# Shift_register_schematic.net
KiCad netlist of a schematic drawn in Altium Designer
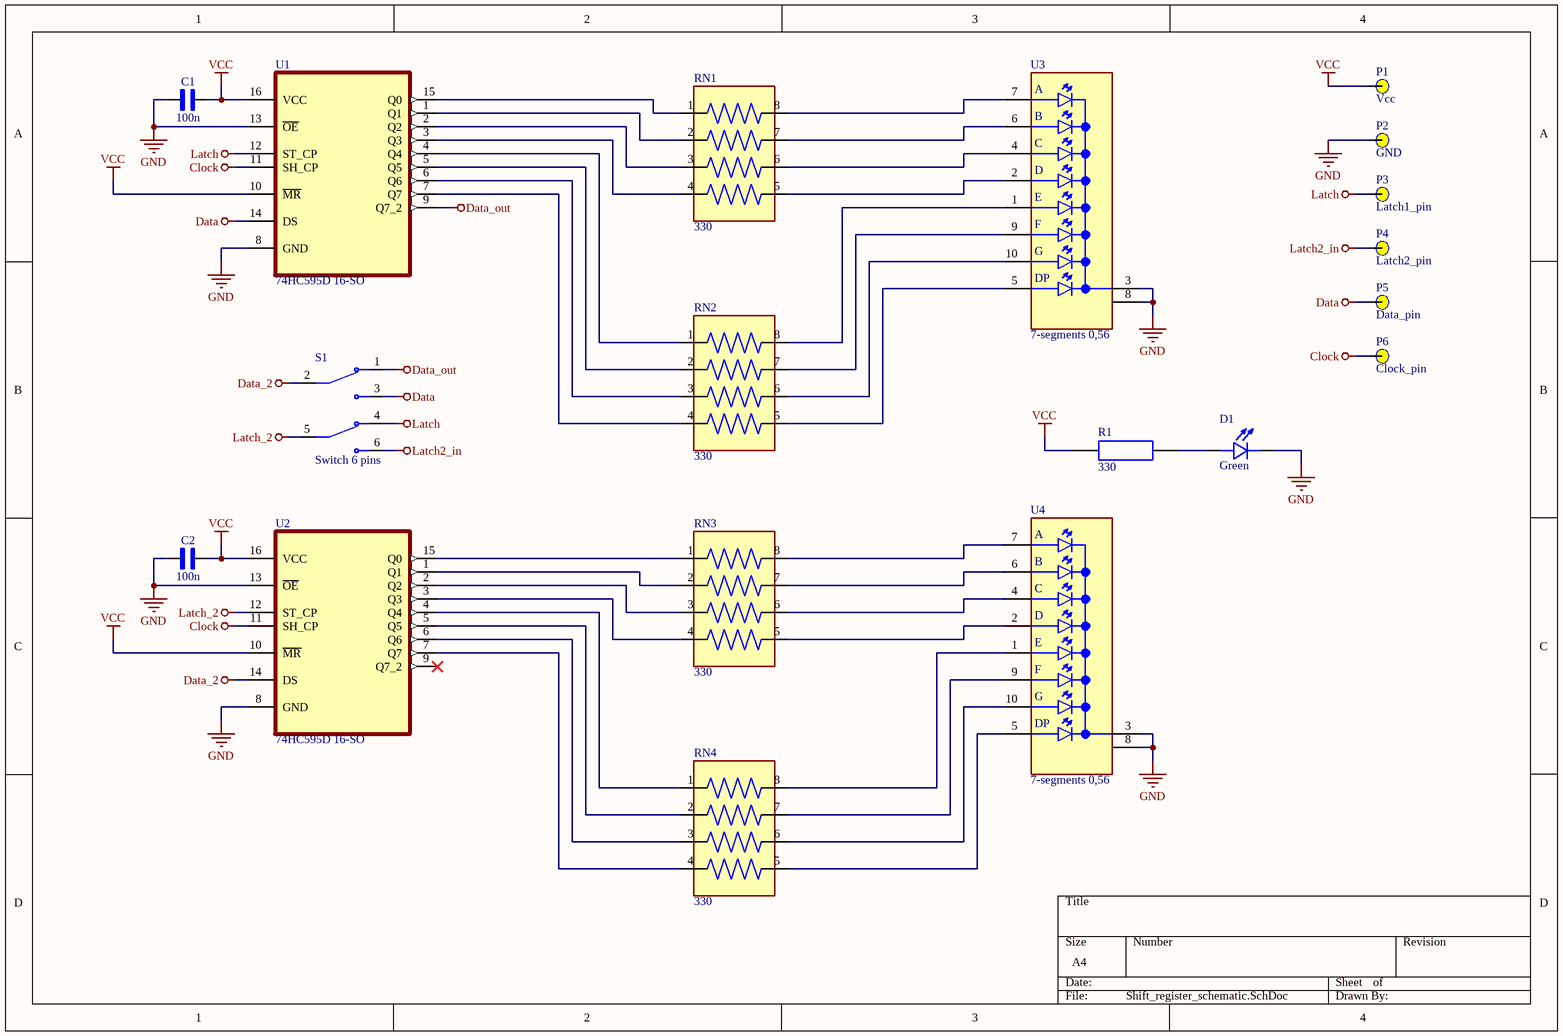
[diagram p0: Shift_register_schematic.SchDoc]

(export (version "E")
  (design (tool "Eeschema 10.0.6"))
  (components
    (comp (ref "C1")
      (value "100n")
      (footprint "Capacitor 1206")
      (fields (field (name "MF") "AVX") (field (name "MP") "12061C225K4T2A"))
      (libsource (lib "Schlib") (part "Capacitor 1206"))
    )
    (comp (ref "C2")
      (value "100n")
      (footprint "Capacitor 1206")
      (fields (field (name "MF") "AVX") (field (name "MP") "12061C225K4T2A"))
      (libsource (lib "Schlib") (part "Capacitor 1206"))
    )
    (comp (ref "D1")
      (value "Green")
      (footprint "LED 1206")
      (fields (field (name "MF") "Lite-On Inc.") (field (name "MP") "LTST-C230KGKT"))
      (libsource (lib "Schlib") (part "LED 1206"))
    )
    (comp (ref "P1") (value "Vcc") (footprint "PCB_Pin_1") (libsource (lib "Schlib") (part "PIN_1")))
    (comp (ref "P2") (value "GND") (footprint "PCB_Pin_1") (libsource (lib "Schlib") (part "PIN_1")))
    (comp (ref "P3") (value "Latch1_pin") (footprint "PCB_Pin_1") (libsource (lib "Schlib") (part "PIN_1")))
    (comp (ref "P4") (value "Latch2_pin") (footprint "PCB_Pin_1") (libsource (lib "Schlib") (part "PIN_1")))
    (comp (ref "P5") (value "Data_pin") (footprint "PCB_Pin_1") (libsource (lib "Schlib") (part "PIN_1")))
    (comp (ref "P6") (value "Clock_pin") (footprint "PCB_Pin_1") (libsource (lib "Schlib") (part "PIN_1")))
    (comp (ref "R1")
      (value "330")
      (footprint "Resistor 1206")
      (fields (field (name "MP") "ERJU08F4703V"))
      (libsource (lib "Schlib") (part "Resistor 1206"))
    )
    (comp (ref "RN1")
      (value "330")
      (footprint "Resistor array 1206")
      (description "Resistor,Thick Film,Networks & Arrays,330 Ohm,5%,8 Pin ¦ Bourns CAY16-331J4LF")
      (fields (field (name "MF") "Bourns") (field (name "MP") "CAY16-331J4LF"))
      (libsource (lib "Schlib") (part "Resistor array 1206"))
    )
    (comp (ref "RN2")
      (value "330")
      (footprint "Resistor array 1206")
      (description "Resistor,Thick Film,Networks & Arrays,330 Ohm,5%,8 Pin ¦ Bourns CAY16-331J4LF")
      (fields (field (name "MF") "Bourns") (field (name "MP") "CAY16-331J4LF"))
      (libsource (lib "Schlib") (part "Resistor array 1206"))
    )
    (comp (ref "RN3")
      (value "330")
      (footprint "Resistor array 1206")
      (description "Resistor,Thick Film,Networks & Arrays,330 Ohm,5%,8 Pin ¦ Bourns CAY16-331J4LF")
      (fields (field (name "MF") "Bourns") (field (name "MP") "CAY16-331J4LF"))
      (libsource (lib "Schlib") (part "Resistor array 1206"))
    )
    (comp (ref "RN4")
      (value "330")
      (footprint "Resistor array 1206")
      (description "Resistor,Thick Film,Networks & Arrays,330 Ohm,5%,8 Pin ¦ Bourns CAY16-331J4LF")
      (fields (field (name "MF") "Bourns") (field (name "MP") "CAY16-331J4LF"))
      (libsource (lib "Schlib") (part "Resistor array 1206"))
    )
    (comp (ref "S1")
      (value "Switch 6 pins")
      (footprint "Switch 6 pins")
      (description "Switch MSK-22D18G2")
      (fields (field (name "MF") "E-Switch") (field (name "MP") "TL2201EEZA"))
      (libsource (lib "Schlib") (part "Switch 6 pins"))
    )
    (comp (ref "U1")
      (value "74HC595D 16-SO")
      (footprint "74HC595 SO-16")
      (description "Shift Shift Register 1 Element 8 Bit 16-SO")
      (fields (field (name "MF") "NXP USA") (field (name "MP") "74HC595D/AUJ"))
      (libsource (lib "Schlib") (part "74HC595D 16-SO"))
    )
    (comp (ref "U2")
      (value "74HC595D 16-SO")
      (footprint "74HC595 SO-16")
      (description "Shift Shift Register 1 Element 8 Bit 16-SO")
      (fields (field (name "MF") "NXP USA") (field (name "MP") "74HC595D/AUJ"))
      (libsource (lib "Schlib") (part "74HC595D 16-SO"))
    )
    (comp (ref "U3")
      (value "7-segments 0,56")
      (footprint "7-segments 0,56")
      (description ".56IN. 7 SEGMENT SINGLE DISPLAY, 565NM GREEN, GRAY FACE, WHITE SEGMENTS, COMMON ¦ Lumex LDS-C512RI")
      (fields (field (name "MF") "Lumex") (field (name "MP") "LDS-C512RI"))
      (libsource (lib "Schlib") (part "7-segments 0,56"))
    )
    (comp (ref "U4")
      (value "7-segments 0,56")
      (footprint "7-segments 0,56")
      (description ".56IN. 7 SEGMENT SINGLE DISPLAY, 565NM GREEN, GRAY FACE, WHITE SEGMENTS, COMMON ¦ Lumex LDS-C512RI")
      (fields (field (name "MF") "Lumex") (field (name "MP") "LDS-C512RI"))
      (libsource (lib "Schlib") (part "7-segments 0,56"))
    )
  )
  (nets
    (net (code "1") (name "Clock") (class "Default")
      (node (ref "P6") (pin "0") (pinfunction "Pin_0") (pintype "passive"))
      (node (ref "U1") (pin "11") (pinfunction "SH_CP_11") (pintype "passive"))
      (node (ref "U2") (pin "11") (pinfunction "SH_CP_11") (pintype "passive"))
    )
    (net (code "2") (name "Data") (class "Default")
      (node (ref "P5") (pin "0") (pinfunction "Pin_0") (pintype "passive"))
      (node (ref "S1") (pin "3") (pinfunction "3_3") (pintype "passive"))
      (node (ref "U1") (pin "14") (pinfunction "DS_14") (pintype "passive"))
    )
    (net (code "3") (name "Data_2") (class "Default")
      (node (ref "S1") (pin "2") (pinfunction "2_2") (pintype "passive"))
      (node (ref "U2") (pin "14") (pinfunction "DS_14") (pintype "passive"))
    )
    (net (code "4") (name "Data_out") (class "Default")
      (node (ref "S1") (pin "1") (pinfunction "1_1") (pintype "passive"))
      (node (ref "U1") (pin "9") (pinfunction "Q7_2_9") (pintype "output"))
    )
    (net (code "5") (name "GND") (class "Default")
      (node (ref "C1") (pin "1") (pinfunction "1_1") (pintype "passive"))
      (node (ref "C2") (pin "1") (pinfunction "1_1") (pintype "passive"))
      (node (ref "D1") (pin "C") (pinfunction "C_C") (pintype "passive"))
      (node (ref "P2") (pin "0") (pinfunction "Pin_0") (pintype "passive"))
      (node (ref "U1") (pin "13") (pinfunction "~{OE}_13") (pintype "passive"))
      (node (ref "U1") (pin "8") (pinfunction "GND_8") (pintype "passive"))
      (node (ref "U2") (pin "13") (pinfunction "~{OE}_13") (pintype "passive"))
      (node (ref "U2") (pin "8") (pinfunction "GND_8") (pintype "passive"))
      (node (ref "U3") (pin "3") (pinfunction "CC_3") (pintype "passive"))
      (node (ref "U3") (pin "8") (pinfunction "CC_8") (pintype "passive"))
      (node (ref "U4") (pin "3") (pinfunction "CC_3") (pintype "passive"))
      (node (ref "U4") (pin "8") (pinfunction "CC_8") (pintype "passive"))
    )
    (net (code "6") (name "Latch") (class "Default")
      (node (ref "P3") (pin "0") (pinfunction "Pin_0") (pintype "passive"))
      (node (ref "S1") (pin "4") (pinfunction "4_4") (pintype "passive"))
      (node (ref "U1") (pin "12") (pinfunction "ST_CP_12") (pintype "passive"))
    )
    (net (code "7") (name "Latch2_in") (class "Default")
      (node (ref "P4") (pin "0") (pinfunction "Pin_0") (pintype "passive"))
      (node (ref "S1") (pin "6") (pinfunction "6_6") (pintype "passive"))
    )
    (net (code "8") (name "Latch_2") (class "Default")
      (node (ref "S1") (pin "5") (pinfunction "5_5") (pintype "passive"))
      (node (ref "U2") (pin "12") (pinfunction "ST_CP_12") (pintype "passive"))
    )
    (net (code "9") (name "Net-(D1-PadA)") (class "Default")
      (node (ref "D1") (pin "A") (pinfunction "A_A") (pintype "passive"))
      (node (ref "R1") (pin "2") (pinfunction "2_2") (pintype "passive"))
    )
    (net (code "10") (name "Net-(U1-Q0)") (class "Default")
      (node (ref "RN1") (pin "1") (pinfunction "1_1") (pintype "passive"))
      (node (ref "U1") (pin "15") (pinfunction "Q0_15") (pintype "output"))
    )
    (net (code "11") (name "Net-(U1-Q1)") (class "Default")
      (node (ref "RN1") (pin "2") (pinfunction "2_2") (pintype "passive"))
      (node (ref "U1") (pin "1") (pinfunction "Q1_1") (pintype "output"))
    )
    (net (code "12") (name "Net-(U1-Q2)") (class "Default")
      (node (ref "RN1") (pin "3") (pinfunction "3_3") (pintype "passive"))
      (node (ref "U1") (pin "2") (pinfunction "Q2_2") (pintype "output"))
    )
    (net (code "13") (name "Net-(U1-Q3)") (class "Default")
      (node (ref "RN1") (pin "4") (pinfunction "4_4") (pintype "passive"))
      (node (ref "U1") (pin "3") (pinfunction "Q3_3") (pintype "output"))
    )
    (net (code "14") (name "Net-(U1-Q4)") (class "Default")
      (node (ref "RN2") (pin "1") (pinfunction "1_1") (pintype "passive"))
      (node (ref "U1") (pin "4") (pinfunction "Q4_4") (pintype "output"))
    )
    (net (code "15") (name "Net-(U1-Q5)") (class "Default")
      (node (ref "RN2") (pin "2") (pinfunction "2_2") (pintype "passive"))
      (node (ref "U1") (pin "5") (pinfunction "Q5_5") (pintype "output"))
    )
    (net (code "16") (name "Net-(U1-Q6)") (class "Default")
      (node (ref "RN2") (pin "3") (pinfunction "3_3") (pintype "passive"))
      (node (ref "U1") (pin "6") (pinfunction "Q6_6") (pintype "output"))
    )
    (net (code "17") (name "Net-(U1-Q7)") (class "Default")
      (node (ref "RN2") (pin "4") (pinfunction "4_4") (pintype "passive"))
      (node (ref "U1") (pin "7") (pinfunction "Q7_7") (pintype "output"))
    )
    (net (code "18") (name "Net-(U2-Q0)") (class "Default")
      (node (ref "RN3") (pin "1") (pinfunction "1_1") (pintype "passive"))
      (node (ref "U2") (pin "15") (pinfunction "Q0_15") (pintype "output"))
    )
    (net (code "19") (name "Net-(U2-Q1)") (class "Default")
      (node (ref "RN3") (pin "2") (pinfunction "2_2") (pintype "passive"))
      (node (ref "U2") (pin "1") (pinfunction "Q1_1") (pintype "output"))
    )
    (net (code "20") (name "Net-(U2-Q2)") (class "Default")
      (node (ref "RN3") (pin "3") (pinfunction "3_3") (pintype "passive"))
      (node (ref "U2") (pin "2") (pinfunction "Q2_2") (pintype "output"))
    )
    (net (code "21") (name "Net-(U2-Q3)") (class "Default")
      (node (ref "RN3") (pin "4") (pinfunction "4_4") (pintype "passive"))
      (node (ref "U2") (pin "3") (pinfunction "Q3_3") (pintype "output"))
    )
    (net (code "22") (name "Net-(U2-Q4)") (class "Default")
      (node (ref "RN4") (pin "1") (pinfunction "1_1") (pintype "passive"))
      (node (ref "U2") (pin "4") (pinfunction "Q4_4") (pintype "output"))
    )
    (net (code "23") (name "Net-(U2-Q5)") (class "Default")
      (node (ref "RN4") (pin "2") (pinfunction "2_2") (pintype "passive"))
      (node (ref "U2") (pin "5") (pinfunction "Q5_5") (pintype "output"))
    )
    (net (code "24") (name "Net-(U2-Q6)") (class "Default")
      (node (ref "RN4") (pin "3") (pinfunction "3_3") (pintype "passive"))
      (node (ref "U2") (pin "6") (pinfunction "Q6_6") (pintype "output"))
    )
    (net (code "25") (name "Net-(U2-Q7)") (class "Default")
      (node (ref "RN4") (pin "4") (pinfunction "4_4") (pintype "passive"))
      (node (ref "U2") (pin "7") (pinfunction "Q7_7") (pintype "output"))
    )
    (net (code "26") (name "Net-(U3-A)") (class "Default")
      (node (ref "RN1") (pin "8") (pinfunction "8_8") (pintype "passive"))
      (node (ref "U3") (pin "7") (pinfunction "A_7") (pintype "passive"))
    )
    (net (code "27") (name "Net-(U3-B)") (class "Default")
      (node (ref "RN1") (pin "7") (pinfunction "7_7") (pintype "passive"))
      (node (ref "U3") (pin "6") (pinfunction "B_6") (pintype "passive"))
    )
    (net (code "28") (name "Net-(U3-C)") (class "Default")
      (node (ref "RN1") (pin "6") (pinfunction "6_6") (pintype "passive"))
      (node (ref "U3") (pin "4") (pinfunction "C_4") (pintype "passive"))
    )
    (net (code "29") (name "Net-(U3-D)") (class "Default")
      (node (ref "RN1") (pin "5") (pinfunction "5_5") (pintype "passive"))
      (node (ref "U3") (pin "2") (pinfunction "D_2") (pintype "passive"))
    )
    (net (code "30") (name "Net-(U3-DP)") (class "Default")
      (node (ref "RN2") (pin "5") (pinfunction "5_5") (pintype "passive"))
      (node (ref "U3") (pin "5") (pinfunction "DP_5") (pintype "passive"))
    )
    (net (code "31") (name "Net-(U3-E)") (class "Default")
      (node (ref "RN2") (pin "8") (pinfunction "8_8") (pintype "passive"))
      (node (ref "U3") (pin "1") (pinfunction "E_1") (pintype "passive"))
    )
    (net (code "32") (name "Net-(U3-F)") (class "Default")
      (node (ref "RN2") (pin "7") (pinfunction "7_7") (pintype "passive"))
      (node (ref "U3") (pin "9") (pinfunction "F_9") (pintype "passive"))
    )
    (net (code "33") (name "Net-(U3-G)") (class "Default")
      (node (ref "RN2") (pin "6") (pinfunction "6_6") (pintype "passive"))
      (node (ref "U3") (pin "10") (pinfunction "G_10") (pintype "passive"))
    )
    (net (code "34") (name "Net-(U4-A)") (class "Default")
      (node (ref "RN3") (pin "8") (pinfunction "8_8") (pintype "passive"))
      (node (ref "U4") (pin "7") (pinfunction "A_7") (pintype "passive"))
    )
    (net (code "35") (name "Net-(U4-B)") (class "Default")
      (node (ref "RN3") (pin "7") (pinfunction "7_7") (pintype "passive"))
      (node (ref "U4") (pin "6") (pinfunction "B_6") (pintype "passive"))
    )
    (net (code "36") (name "Net-(U4-C)") (class "Default")
      (node (ref "RN3") (pin "6") (pinfunction "6_6") (pintype "passive"))
      (node (ref "U4") (pin "4") (pinfunction "C_4") (pintype "passive"))
    )
    (net (code "37") (name "Net-(U4-D)") (class "Default")
      (node (ref "RN3") (pin "5") (pinfunction "5_5") (pintype "passive"))
      (node (ref "U4") (pin "2") (pinfunction "D_2") (pintype "passive"))
    )
    (net (code "38") (name "Net-(U4-DP)") (class "Default")
      (node (ref "RN4") (pin "5") (pinfunction "5_5") (pintype "passive"))
      (node (ref "U4") (pin "5") (pinfunction "DP_5") (pintype "passive"))
    )
    (net (code "39") (name "Net-(U4-E)") (class "Default")
      (node (ref "RN4") (pin "8") (pinfunction "8_8") (pintype "passive"))
      (node (ref "U4") (pin "1") (pinfunction "E_1") (pintype "passive"))
    )
    (net (code "40") (name "Net-(U4-F)") (class "Default")
      (node (ref "RN4") (pin "7") (pinfunction "7_7") (pintype "passive"))
      (node (ref "U4") (pin "9") (pinfunction "F_9") (pintype "passive"))
    )
    (net (code "41") (name "Net-(U4-G)") (class "Default")
      (node (ref "RN4") (pin "6") (pinfunction "6_6") (pintype "passive"))
      (node (ref "U4") (pin "10") (pinfunction "G_10") (pintype "passive"))
    )
    (net (code "42") (name "VCC") (class "Default")
      (node (ref "C1") (pin "2") (pinfunction "2_2") (pintype "passive"))
      (node (ref "C2") (pin "2") (pinfunction "2_2") (pintype "passive"))
      (node (ref "P1") (pin "0") (pinfunction "Pin_0") (pintype "passive"))
      (node (ref "R1") (pin "1") (pinfunction "1_1") (pintype "passive"))
      (node (ref "U1") (pin "10") (pinfunction "~{MR}_10") (pintype "passive"))
      (node (ref "U1") (pin "16") (pinfunction "VCC_16") (pintype "power_in"))
      (node (ref "U2") (pin "10") (pinfunction "~{MR}_10") (pintype "passive"))
      (node (ref "U2") (pin "16") (pinfunction "VCC_16") (pintype "power_in"))
    )
    (net (code "43") (name "unconnected-(U2-Q7_2-Pad9)") (class "Default")
      (node (ref "U2") (pin "9") (pinfunction "Q7_2_9") (pintype "output+no_connect"))
    )
  )
)
